# Level-Shifter-6_v10.net
KiCad netlist of a schematic drawn in EAGLE
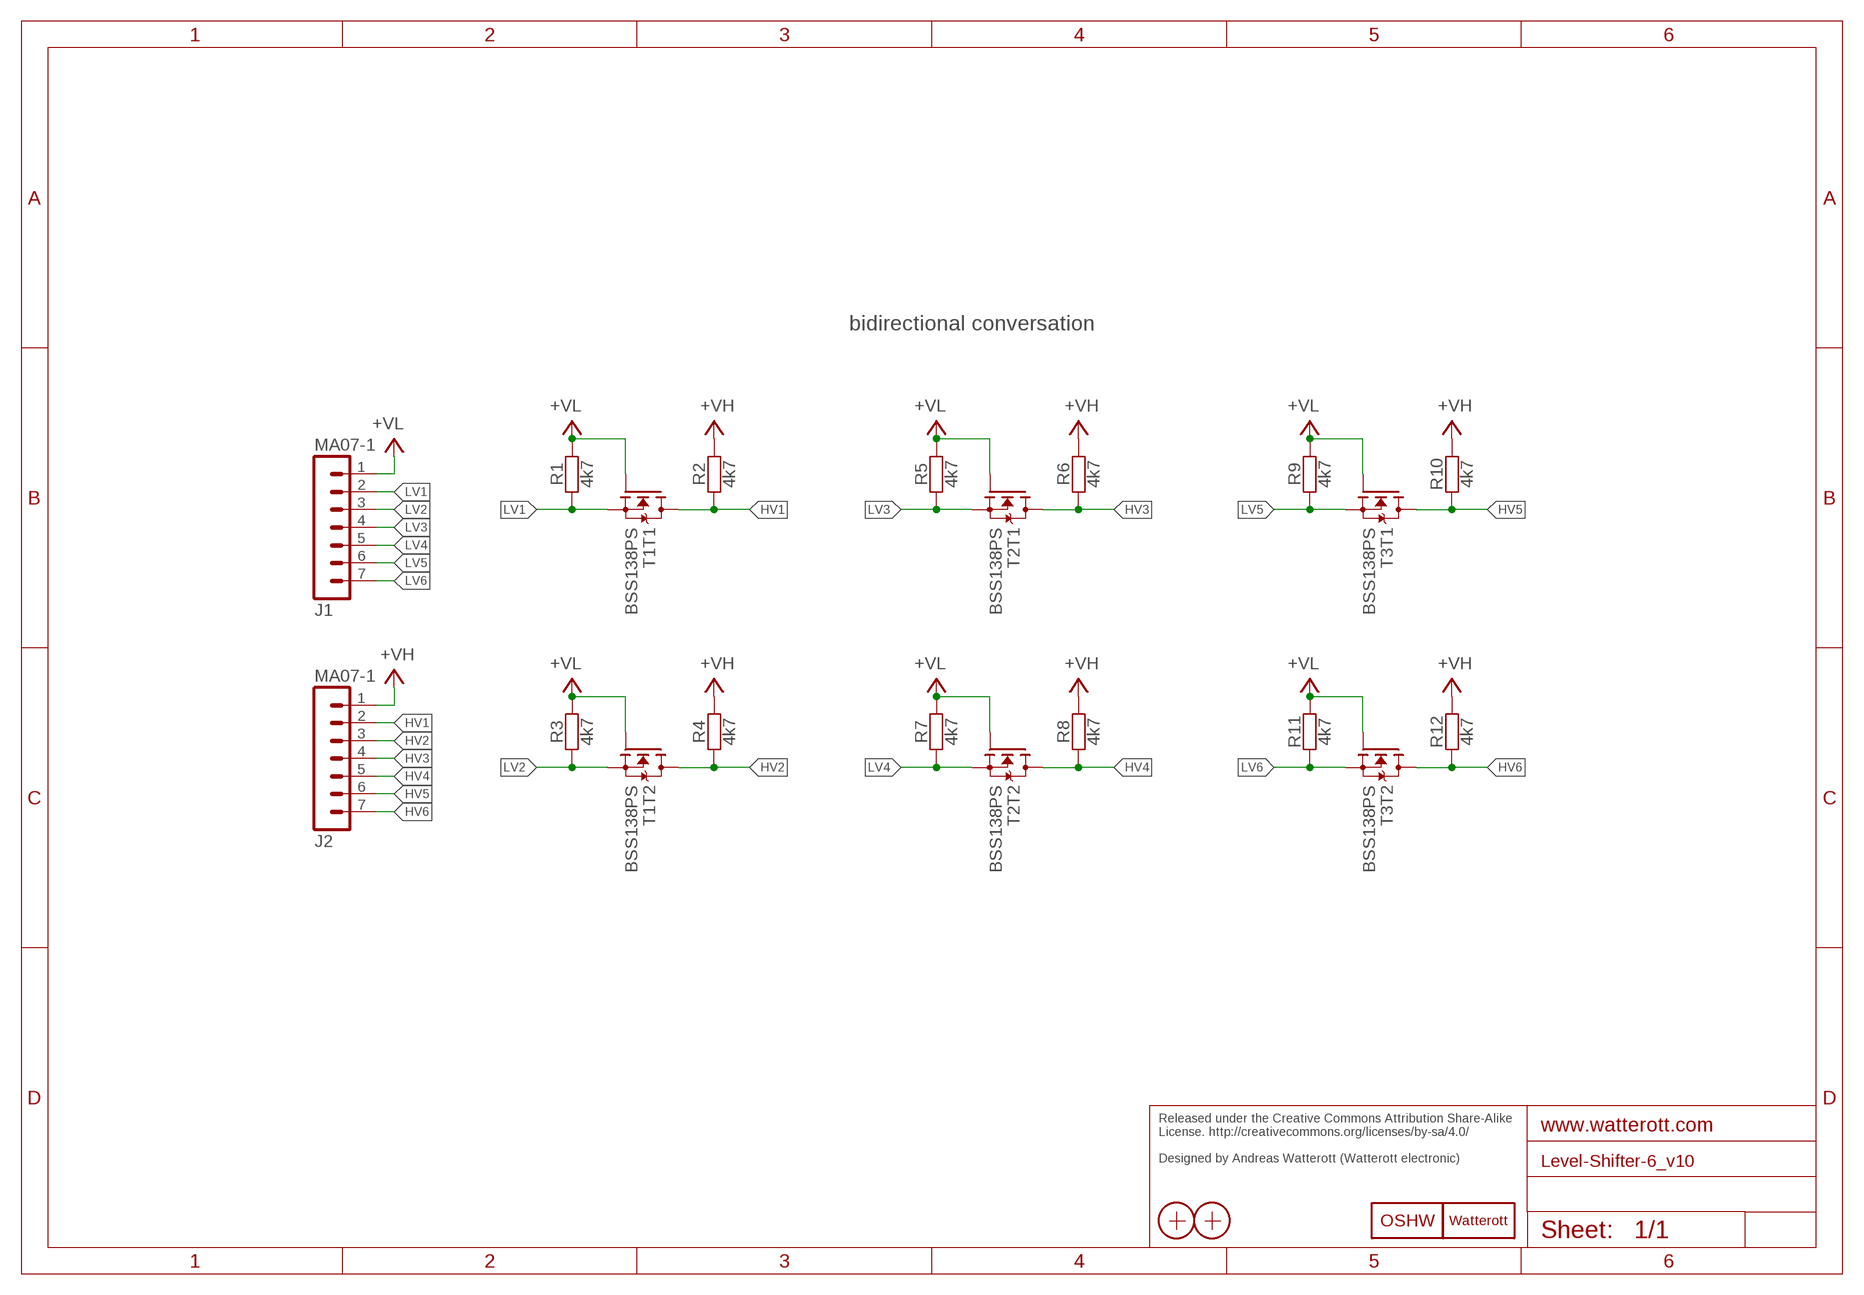
[diagram p0: schematic, sheet 1]

(export (version "E")
  (design (tool "Eeschema 10.0.6"))
  (components
    (comp (ref "J1")
      (value "MA07-1")
      (footprint "eagle-import:MA07-1")
      (libsource (lib "eagle-import") (part "MA07-1"))
    )
    (comp (ref "J2")
      (value "MA07-1")
      (footprint "eagle-import:MA07-1")
      (libsource (lib "eagle-import") (part "MA07-1"))
    )
    (comp (ref "LOGO1")
      (value "OSHW_LOGOX0070")
      (footprint "eagle-import:OSHW_6X70")
      (libsource (lib "eagle-import") (part "OSHW_LOGOX0070"))
    )
    (comp (ref "LOGO2")
      (value "LOGO-S_PLACE_S")
      (footprint "eagle-import:SPARK_TPLACE_S")
      (libsource (lib "eagle-import") (part "LOGO-S_PLACE_S"))
    )
    (comp (ref "R1")
      (value "4k7")
      (footprint "eagle-import:C0402")
      (libsource (lib "eagle-import") (part "RESISTOR-0402"))
    )
    (comp (ref "R2")
      (value "4k7")
      (footprint "eagle-import:C0402")
      (libsource (lib "eagle-import") (part "RESISTOR-0402"))
    )
    (comp (ref "R3")
      (value "4k7")
      (footprint "eagle-import:C0402")
      (libsource (lib "eagle-import") (part "RESISTOR-0402"))
    )
    (comp (ref "R4")
      (value "4k7")
      (footprint "eagle-import:C0402")
      (libsource (lib "eagle-import") (part "RESISTOR-0402"))
    )
    (comp (ref "R5")
      (value "4k7")
      (footprint "eagle-import:C0402")
      (libsource (lib "eagle-import") (part "RESISTOR-0402"))
    )
    (comp (ref "R6")
      (value "4k7")
      (footprint "eagle-import:C0402")
      (libsource (lib "eagle-import") (part "RESISTOR-0402"))
    )
    (comp (ref "R7")
      (value "4k7")
      (footprint "eagle-import:C0402")
      (libsource (lib "eagle-import") (part "RESISTOR-0402"))
    )
    (comp (ref "R8")
      (value "4k7")
      (footprint "eagle-import:C0402")
      (libsource (lib "eagle-import") (part "RESISTOR-0402"))
    )
    (comp (ref "R9")
      (value "4k7")
      (footprint "eagle-import:C0402")
      (libsource (lib "eagle-import") (part "RESISTOR-0402"))
    )
    (comp (ref "R10")
      (value "4k7")
      (footprint "eagle-import:C0402")
      (libsource (lib "eagle-import") (part "RESISTOR-0402"))
    )
    (comp (ref "R11")
      (value "4k7")
      (footprint "eagle-import:C0402")
      (libsource (lib "eagle-import") (part "RESISTOR-0402"))
    )
    (comp (ref "R12")
      (value "4k7")
      (footprint "eagle-import:C0402")
      (libsource (lib "eagle-import") (part "RESISTOR-0402"))
    )
    (comp (ref "T1")
      (value "BSS138PS")
      (footprint "eagle-import:SOT363")
      (libsource (lib "eagle-import") (part "BSS138PS"))
    )
    (comp (ref "T2")
      (value "BSS138PS")
      (footprint "eagle-import:SOT363")
      (libsource (lib "eagle-import") (part "BSS138PS"))
    )
    (comp (ref "T3")
      (value "BSS138PS")
      (footprint "eagle-import:SOT363")
      (libsource (lib "eagle-import") (part "BSS138PS"))
    )
    (comp (ref "X1")
      (value "PASSER-07")
      (footprint "eagle-import:PASSER_07MM")
      (libsource (lib "eagle-import") (part "PASSER-07"))
    )
    (comp (ref "X2")
      (value "PASSER-07")
      (footprint "eagle-import:PASSER_07MM")
      (libsource (lib "eagle-import") (part "PASSER-07"))
    )
  )
  (nets
    (net (code "1") (name "+VH") (class "Default")
      (node (ref "J2") (pin "1") (pinfunction "1_1") (pintype "passive"))
      (node (ref "R10") (pin "2") (pinfunction "2_2") (pintype "passive"))
      (node (ref "R12") (pin "2") (pinfunction "2_2") (pintype "passive"))
      (node (ref "R2") (pin "2") (pinfunction "2_2") (pintype "passive"))
      (node (ref "R4") (pin "2") (pinfunction "2_2") (pintype "passive"))
      (node (ref "R6") (pin "2") (pinfunction "2_2") (pintype "passive"))
      (node (ref "R8") (pin "2") (pinfunction "2_2") (pintype "passive"))
    )
    (net (code "2") (name "+VL") (class "Default")
      (node (ref "J1") (pin "1") (pinfunction "1_1") (pintype "passive"))
      (node (ref "R1") (pin "2") (pinfunction "2_2") (pintype "passive"))
      (node (ref "R11") (pin "2") (pinfunction "2_2") (pintype "passive"))
      (node (ref "R3") (pin "2") (pinfunction "2_2") (pintype "passive"))
      (node (ref "R5") (pin "2") (pinfunction "2_2") (pintype "passive"))
      (node (ref "R7") (pin "2") (pinfunction "2_2") (pintype "passive"))
      (node (ref "R9") (pin "2") (pinfunction "2_2") (pintype "passive"))
      (node (ref "T1") (pin "2") (pinfunction "G_2") (pintype "passive"))
      (node (ref "T1") (pin "5") (pinfunction "G_5") (pintype "passive"))
      (node (ref "T2") (pin "2") (pinfunction "G_2") (pintype "passive"))
      (node (ref "T2") (pin "5") (pinfunction "G_5") (pintype "passive"))
      (node (ref "T3") (pin "2") (pinfunction "G_2") (pintype "passive"))
      (node (ref "T3") (pin "5") (pinfunction "G_5") (pintype "passive"))
    )
    (net (code "3") (name "HV1") (class "Default")
      (node (ref "J2") (pin "2") (pinfunction "2_2") (pintype "passive"))
      (node (ref "R2") (pin "1") (pinfunction "1_1") (pintype "passive"))
      (node (ref "T1") (pin "6") (pinfunction "D_6") (pintype "passive"))
    )
    (net (code "4") (name "HV2") (class "Default")
      (node (ref "J2") (pin "3") (pinfunction "3_3") (pintype "passive"))
      (node (ref "R4") (pin "1") (pinfunction "1_1") (pintype "passive"))
      (node (ref "T1") (pin "3") (pinfunction "D_3") (pintype "passive"))
    )
    (net (code "5") (name "HV3") (class "Default")
      (node (ref "J2") (pin "4") (pinfunction "4_4") (pintype "passive"))
      (node (ref "R6") (pin "1") (pinfunction "1_1") (pintype "passive"))
      (node (ref "T2") (pin "6") (pinfunction "D_6") (pintype "passive"))
    )
    (net (code "6") (name "HV4") (class "Default")
      (node (ref "J2") (pin "5") (pinfunction "5_5") (pintype "passive"))
      (node (ref "R8") (pin "1") (pinfunction "1_1") (pintype "passive"))
      (node (ref "T2") (pin "3") (pinfunction "D_3") (pintype "passive"))
    )
    (net (code "7") (name "HV5") (class "Default")
      (node (ref "J2") (pin "6") (pinfunction "6_6") (pintype "passive"))
      (node (ref "R10") (pin "1") (pinfunction "1_1") (pintype "passive"))
      (node (ref "T3") (pin "6") (pinfunction "D_6") (pintype "passive"))
    )
    (net (code "8") (name "HV6") (class "Default")
      (node (ref "J2") (pin "7") (pinfunction "7_7") (pintype "passive"))
      (node (ref "R12") (pin "1") (pinfunction "1_1") (pintype "passive"))
      (node (ref "T3") (pin "3") (pinfunction "D_3") (pintype "passive"))
    )
    (net (code "9") (name "LV1") (class "Default")
      (node (ref "J1") (pin "2") (pinfunction "2_2") (pintype "passive"))
      (node (ref "R1") (pin "1") (pinfunction "1_1") (pintype "passive"))
      (node (ref "T1") (pin "1") (pinfunction "S_1") (pintype "passive"))
    )
    (net (code "10") (name "LV2") (class "Default")
      (node (ref "J1") (pin "3") (pinfunction "3_3") (pintype "passive"))
      (node (ref "R3") (pin "1") (pinfunction "1_1") (pintype "passive"))
      (node (ref "T1") (pin "4") (pinfunction "S_4") (pintype "passive"))
    )
    (net (code "11") (name "LV3") (class "Default")
      (node (ref "J1") (pin "4") (pinfunction "4_4") (pintype "passive"))
      (node (ref "R5") (pin "1") (pinfunction "1_1") (pintype "passive"))
      (node (ref "T2") (pin "1") (pinfunction "S_1") (pintype "passive"))
    )
    (net (code "12") (name "LV4") (class "Default")
      (node (ref "J1") (pin "5") (pinfunction "5_5") (pintype "passive"))
      (node (ref "R7") (pin "1") (pinfunction "1_1") (pintype "passive"))
      (node (ref "T2") (pin "4") (pinfunction "S_4") (pintype "passive"))
    )
    (net (code "13") (name "LV5") (class "Default")
      (node (ref "J1") (pin "6") (pinfunction "6_6") (pintype "passive"))
      (node (ref "R9") (pin "1") (pinfunction "1_1") (pintype "passive"))
      (node (ref "T3") (pin "1") (pinfunction "S_1") (pintype "passive"))
    )
    (net (code "14") (name "LV6") (class "Default")
      (node (ref "J1") (pin "7") (pinfunction "7_7") (pintype "passive"))
      (node (ref "R11") (pin "1") (pinfunction "1_1") (pintype "passive"))
      (node (ref "T3") (pin "4") (pinfunction "S_4") (pintype "passive"))
    )
  )
)
